# halogen-led.net
KiCad netlist of a schematic drawn in EAGLE
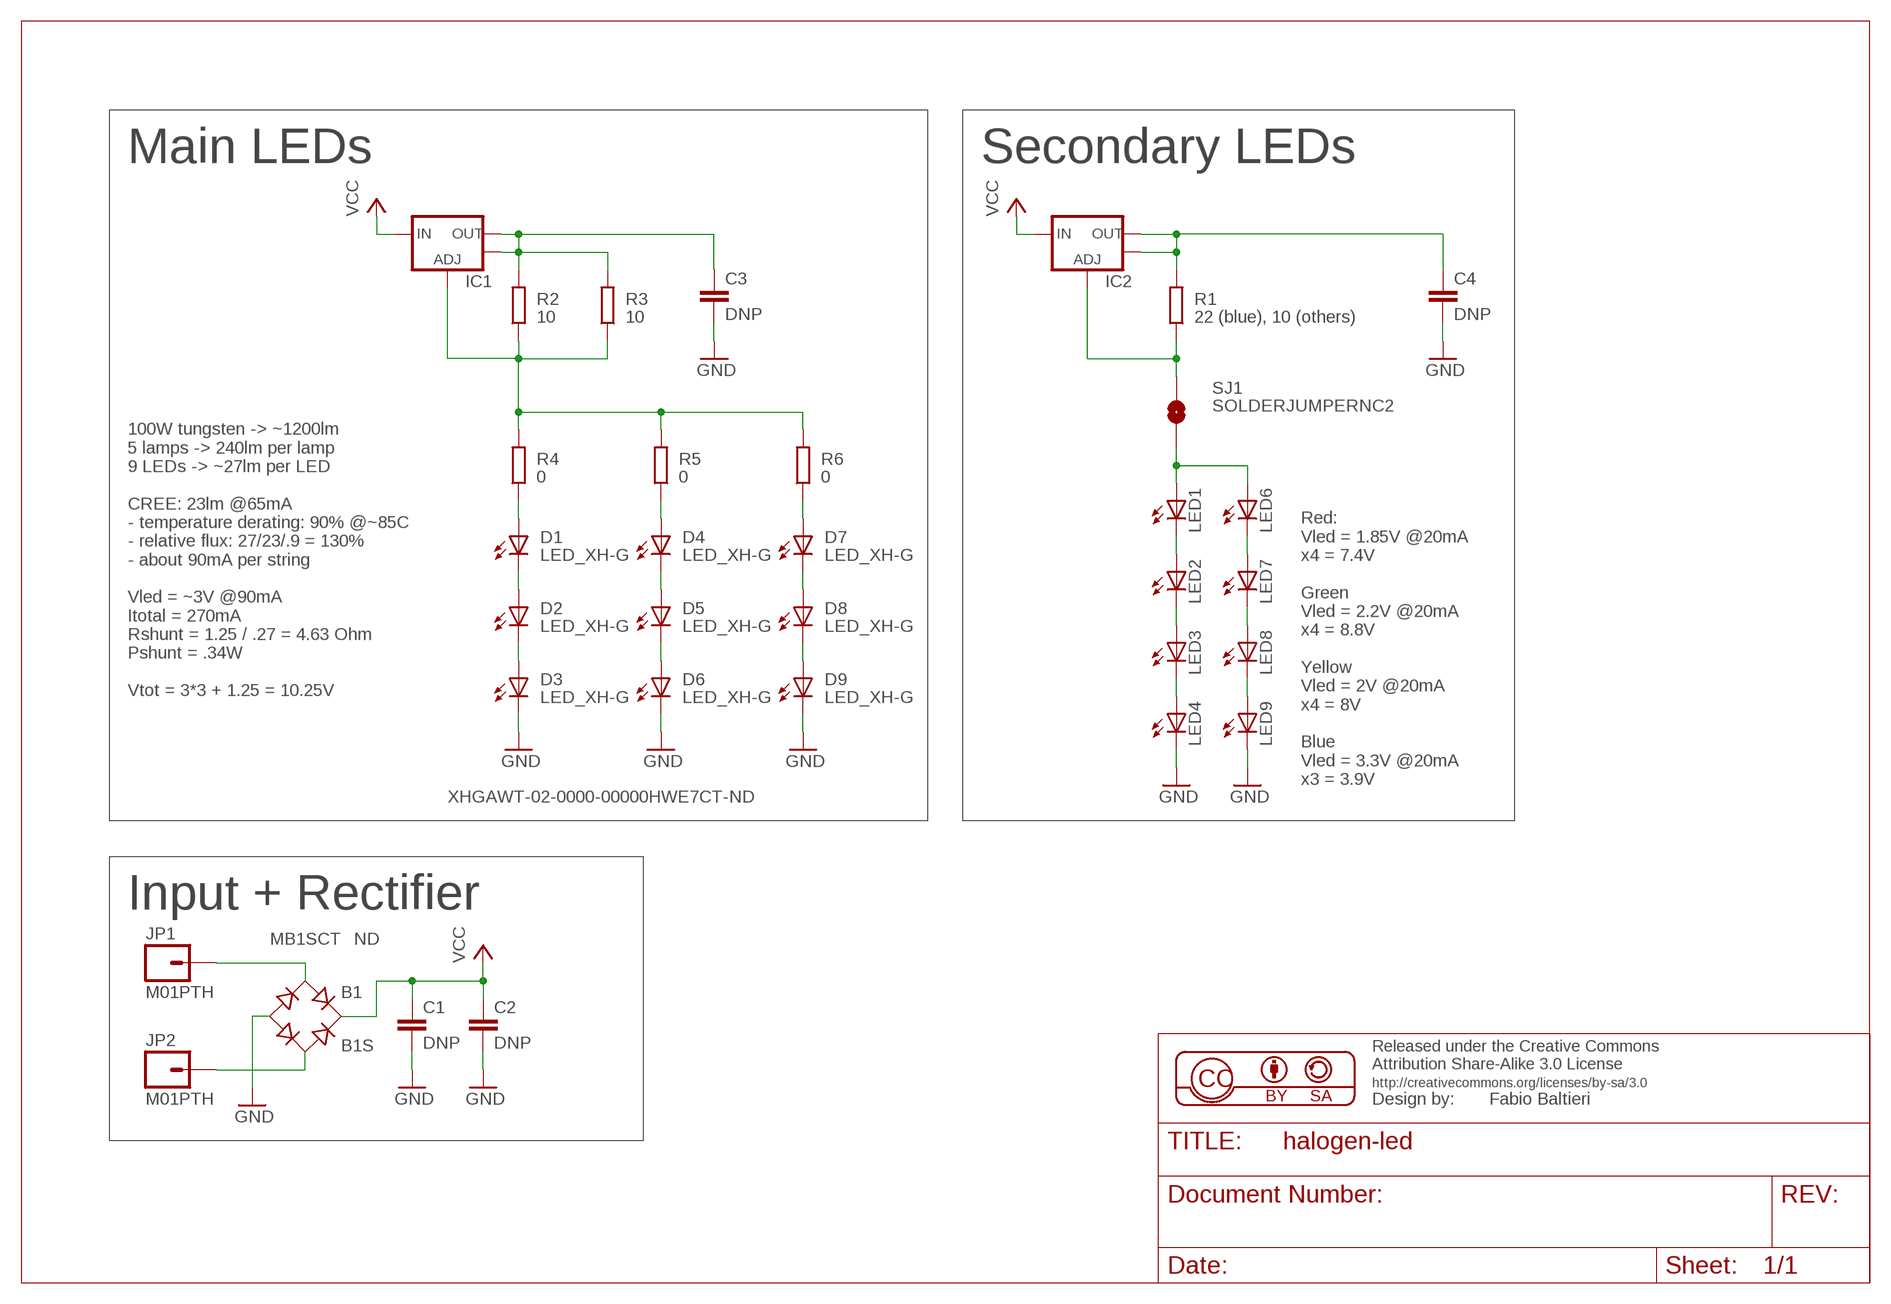
[diagram p0: schematic, sheet 1]

(export (version "E")
  (design (tool "Eeschema 10.0.6"))
  (components
    (comp (ref "B1")
      (value "B1S")
      (footprint "eagle-import:MBS")
      (libsource (lib "eagle-import") (part "BS1"))
    )
    (comp (ref "C1")
      (value "DNP")
      (footprint "eagle-import:C1206")
      (libsource (lib "eagle-import") (part "C-EUC1206"))
    )
    (comp (ref "C2")
      (value "DNP")
      (footprint "eagle-import:C1206")
      (libsource (lib "eagle-import") (part "C-EUC1206"))
    )
    (comp (ref "C3")
      (value "DNP")
      (footprint "eagle-import:C0805")
      (libsource (lib "eagle-import") (part "C-EUC0805"))
    )
    (comp (ref "C4")
      (value "DNP")
      (footprint "eagle-import:C0805")
      (libsource (lib "eagle-import") (part "C-EUC0805"))
    )
    (comp (ref "D1")
      (value "LED_XH-G")
      (footprint "eagle-import:CREE_XHG")
      (libsource (lib "eagle-import") (part "LED_XH-G"))
    )
    (comp (ref "D2")
      (value "LED_XH-G")
      (footprint "eagle-import:CREE_XHG")
      (libsource (lib "eagle-import") (part "LED_XH-G"))
    )
    (comp (ref "D3")
      (value "LED_XH-G")
      (footprint "eagle-import:CREE_XHG")
      (libsource (lib "eagle-import") (part "LED_XH-G"))
    )
    (comp (ref "D4")
      (value "LED_XH-G")
      (footprint "eagle-import:CREE_XHG")
      (libsource (lib "eagle-import") (part "LED_XH-G"))
    )
    (comp (ref "D5")
      (value "LED_XH-G")
      (footprint "eagle-import:CREE_XHG")
      (libsource (lib "eagle-import") (part "LED_XH-G"))
    )
    (comp (ref "D6")
      (value "LED_XH-G")
      (footprint "eagle-import:CREE_XHG")
      (libsource (lib "eagle-import") (part "LED_XH-G"))
    )
    (comp (ref "D7")
      (value "LED_XH-G")
      (footprint "eagle-import:CREE_XHG")
      (libsource (lib "eagle-import") (part "LED_XH-G"))
    )
    (comp (ref "D8")
      (value "LED_XH-G")
      (footprint "eagle-import:CREE_XHG")
      (libsource (lib "eagle-import") (part "LED_XH-G"))
    )
    (comp (ref "D9")
      (value "LED_XH-G")
      (footprint "eagle-import:CREE_XHG")
      (libsource (lib "eagle-import") (part "LED_XH-G"))
    )
    (comp (ref "IC1")
      (value "V_REG_LM1117SOT223")
      (footprint "eagle-import:SOT223")
      (libsource (lib "eagle-import") (part "V_REG_LM1117SOT223"))
    )
    (comp (ref "IC2")
      (value "V_REG_LM1117SOT223")
      (footprint "eagle-import:SOT223")
      (libsource (lib "eagle-import") (part "V_REG_LM1117SOT223"))
    )
    (comp (ref "JP1")
      (value "M01PTH")
      (footprint "eagle-import:1X01")
      (libsource (lib "eagle-import") (part "M01PTH"))
    )
    (comp (ref "JP2")
      (value "M01PTH")
      (footprint "eagle-import:1X01")
      (libsource (lib "eagle-import") (part "M01PTH"))
    )
    (comp (ref "LED1")
      (value "LEDCHIPLED_0805")
      (footprint "eagle-import:CHIPLED_0805")
      (libsource (lib "eagle-import") (part "LEDCHIPLED_0805"))
    )
    (comp (ref "LED2")
      (value "LEDCHIPLED_0805")
      (footprint "eagle-import:CHIPLED_0805")
      (libsource (lib "eagle-import") (part "LEDCHIPLED_0805"))
    )
    (comp (ref "LED3")
      (value "LEDCHIPLED_0805")
      (footprint "eagle-import:CHIPLED_0805")
      (libsource (lib "eagle-import") (part "LEDCHIPLED_0805"))
    )
    (comp (ref "LED4")
      (value "LEDCHIPLED_0805")
      (footprint "eagle-import:CHIPLED_0805")
      (libsource (lib "eagle-import") (part "LEDCHIPLED_0805"))
    )
    (comp (ref "LED6")
      (value "LEDCHIPLED_0805")
      (footprint "eagle-import:CHIPLED_0805")
      (libsource (lib "eagle-import") (part "LEDCHIPLED_0805"))
    )
    (comp (ref "LED7")
      (value "LEDCHIPLED_0805")
      (footprint "eagle-import:CHIPLED_0805")
      (libsource (lib "eagle-import") (part "LEDCHIPLED_0805"))
    )
    (comp (ref "LED8")
      (value "LEDCHIPLED_0805")
      (footprint "eagle-import:CHIPLED_0805")
      (libsource (lib "eagle-import") (part "LEDCHIPLED_0805"))
    )
    (comp (ref "LED9")
      (value "LEDCHIPLED_0805")
      (footprint "eagle-import:CHIPLED_0805")
      (libsource (lib "eagle-import") (part "LEDCHIPLED_0805"))
    )
    (comp (ref "R1")
      (value "22 (blue), 10 (others)")
      (footprint "eagle-import:R1206")
      (libsource (lib "eagle-import") (part "R-EU_R1206"))
    )
    (comp (ref "R2")
      (value "10")
      (footprint "eagle-import:R1206")
      (libsource (lib "eagle-import") (part "R-EU_R1206"))
    )
    (comp (ref "R3")
      (value "10")
      (footprint "eagle-import:R1206")
      (libsource (lib "eagle-import") (part "R-EU_R1206"))
    )
    (comp (ref "R4")
      (value "0")
      (footprint "eagle-import:R0805")
      (libsource (lib "eagle-import") (part "R-EU_R0805"))
    )
    (comp (ref "R5")
      (value "0")
      (footprint "eagle-import:R0805")
      (libsource (lib "eagle-import") (part "R-EU_R0805"))
    )
    (comp (ref "R6")
      (value "0")
      (footprint "eagle-import:R0805")
      (libsource (lib "eagle-import") (part "R-EU_R0805"))
    )
    (comp (ref "SJ1")
      (value "SOLDERJUMPERNC2")
      (footprint "eagle-import:SJ_2S-NOTRACE")
      (libsource (lib "eagle-import") (part "SOLDERJUMPERNC2"))
    )
  )
  (nets
    (net (code "1") (name "GND") (class "Default")
      (node (ref "B1") (pin "-") (pinfunction "-_-") (pintype "passive"))
      (node (ref "C1") (pin "2") (pinfunction "2_2") (pintype "passive"))
      (node (ref "C2") (pin "2") (pinfunction "2_2") (pintype "passive"))
      (node (ref "C3") (pin "2") (pinfunction "2_2") (pintype "passive"))
      (node (ref "C4") (pin "2") (pinfunction "2_2") (pintype "passive"))
      (node (ref "D3") (pin "C") (pinfunction "C_C") (pintype "passive"))
      (node (ref "D3") (pin "C@1") (pinfunction "C_C@1") (pintype "passive"))
      (node (ref "D6") (pin "C") (pinfunction "C_C") (pintype "passive"))
      (node (ref "D6") (pin "C@1") (pinfunction "C_C@1") (pintype "passive"))
      (node (ref "D9") (pin "C") (pinfunction "C_C") (pintype "passive"))
      (node (ref "D9") (pin "C@1") (pinfunction "C_C@1") (pintype "passive"))
      (node (ref "LED4") (pin "C") (pinfunction "C_C") (pintype "passive"))
      (node (ref "LED9") (pin "C") (pinfunction "C_C") (pintype "passive"))
    )
    (net (code "2") (name "Net-(B1-PadAC1)") (class "Default")
      (node (ref "B1") (pin "AC1") (pinfunction "AC1_AC1") (pintype "passive"))
      (node (ref "JP1") (pin "1") (pinfunction "1_1") (pintype "passive"))
    )
    (net (code "3") (name "Net-(B1-PadAC2)") (class "Default")
      (node (ref "B1") (pin "AC2") (pinfunction "AC2_AC2") (pintype "passive"))
      (node (ref "JP2") (pin "1") (pinfunction "1_1") (pintype "passive"))
    )
    (net (code "4") (name "Net-(C3-Pad1)") (class "Default")
      (node (ref "C3") (pin "1") (pinfunction "1_1") (pintype "passive"))
      (node (ref "IC1") (pin "2") (pinfunction "OUT_2") (pintype "output"))
      (node (ref "IC1") (pin "4") (pinfunction "OUT_4") (pintype "output"))
      (node (ref "R2") (pin "2") (pinfunction "2_2") (pintype "passive"))
      (node (ref "R3") (pin "2") (pinfunction "2_2") (pintype "passive"))
    )
    (net (code "5") (name "Net-(C4-Pad1)") (class "Default")
      (node (ref "C4") (pin "1") (pinfunction "1_1") (pintype "passive"))
      (node (ref "IC2") (pin "2") (pinfunction "OUT_2") (pintype "output"))
      (node (ref "IC2") (pin "4") (pinfunction "OUT_4") (pintype "output"))
      (node (ref "R1") (pin "2") (pinfunction "2_2") (pintype "passive"))
    )
    (net (code "6") (name "Net-(D1-A-PadA@1)") (class "Default")
      (node (ref "D1") (pin "A") (pinfunction "A_A") (pintype "passive"))
      (node (ref "D1") (pin "A@1") (pinfunction "A_A@1") (pintype "passive"))
      (node (ref "R4") (pin "1") (pinfunction "1_1") (pintype "passive"))
    )
    (net (code "7") (name "Net-(D1-C-PadC@1)") (class "Default")
      (node (ref "D1") (pin "C") (pinfunction "C_C") (pintype "passive"))
      (node (ref "D1") (pin "C@1") (pinfunction "C_C@1") (pintype "passive"))
      (node (ref "D2") (pin "A") (pinfunction "A_A") (pintype "passive"))
      (node (ref "D2") (pin "A@1") (pinfunction "A_A@1") (pintype "passive"))
    )
    (net (code "8") (name "Net-(D2-C-PadC@1)") (class "Default")
      (node (ref "D2") (pin "C") (pinfunction "C_C") (pintype "passive"))
      (node (ref "D2") (pin "C@1") (pinfunction "C_C@1") (pintype "passive"))
      (node (ref "D3") (pin "A") (pinfunction "A_A") (pintype "passive"))
      (node (ref "D3") (pin "A@1") (pinfunction "A_A@1") (pintype "passive"))
    )
    (net (code "9") (name "Net-(D4-A-PadA@1)") (class "Default")
      (node (ref "D4") (pin "A") (pinfunction "A_A") (pintype "passive"))
      (node (ref "D4") (pin "A@1") (pinfunction "A_A@1") (pintype "passive"))
      (node (ref "R5") (pin "1") (pinfunction "1_1") (pintype "passive"))
    )
    (net (code "10") (name "Net-(D4-C-PadC@1)") (class "Default")
      (node (ref "D4") (pin "C") (pinfunction "C_C") (pintype "passive"))
      (node (ref "D4") (pin "C@1") (pinfunction "C_C@1") (pintype "passive"))
      (node (ref "D5") (pin "A") (pinfunction "A_A") (pintype "passive"))
      (node (ref "D5") (pin "A@1") (pinfunction "A_A@1") (pintype "passive"))
    )
    (net (code "11") (name "Net-(D5-C-PadC@1)") (class "Default")
      (node (ref "D5") (pin "C") (pinfunction "C_C") (pintype "passive"))
      (node (ref "D5") (pin "C@1") (pinfunction "C_C@1") (pintype "passive"))
      (node (ref "D6") (pin "A") (pinfunction "A_A") (pintype "passive"))
      (node (ref "D6") (pin "A@1") (pinfunction "A_A@1") (pintype "passive"))
    )
    (net (code "12") (name "Net-(D7-A-PadA@1)") (class "Default")
      (node (ref "D7") (pin "A") (pinfunction "A_A") (pintype "passive"))
      (node (ref "D7") (pin "A@1") (pinfunction "A_A@1") (pintype "passive"))
      (node (ref "R6") (pin "1") (pinfunction "1_1") (pintype "passive"))
    )
    (net (code "13") (name "Net-(D7-C-PadC@1)") (class "Default")
      (node (ref "D7") (pin "C") (pinfunction "C_C") (pintype "passive"))
      (node (ref "D7") (pin "C@1") (pinfunction "C_C@1") (pintype "passive"))
      (node (ref "D8") (pin "A") (pinfunction "A_A") (pintype "passive"))
      (node (ref "D8") (pin "A@1") (pinfunction "A_A@1") (pintype "passive"))
    )
    (net (code "14") (name "Net-(D8-C-PadC@1)") (class "Default")
      (node (ref "D8") (pin "C") (pinfunction "C_C") (pintype "passive"))
      (node (ref "D8") (pin "C@1") (pinfunction "C_C@1") (pintype "passive"))
      (node (ref "D9") (pin "A") (pinfunction "A_A") (pintype "passive"))
      (node (ref "D9") (pin "A@1") (pinfunction "A_A@1") (pintype "passive"))
    )
    (net (code "15") (name "Net-(IC1-ADJ)") (class "Default")
      (node (ref "IC1") (pin "1") (pinfunction "ADJ_1") (pintype "input"))
      (node (ref "R2") (pin "1") (pinfunction "1_1") (pintype "passive"))
      (node (ref "R3") (pin "1") (pinfunction "1_1") (pintype "passive"))
      (node (ref "R4") (pin "2") (pinfunction "2_2") (pintype "passive"))
      (node (ref "R5") (pin "2") (pinfunction "2_2") (pintype "passive"))
      (node (ref "R6") (pin "2") (pinfunction "2_2") (pintype "passive"))
    )
    (net (code "16") (name "Net-(IC2-ADJ)") (class "Default")
      (node (ref "IC2") (pin "1") (pinfunction "ADJ_1") (pintype "input"))
      (node (ref "R1") (pin "1") (pinfunction "1_1") (pintype "passive"))
      (node (ref "SJ1") (pin "1") (pinfunction "1_1") (pintype "passive"))
    )
    (net (code "17") (name "Net-(LED1-PadA)") (class "Default")
      (node (ref "LED1") (pin "A") (pinfunction "A_A") (pintype "passive"))
      (node (ref "LED6") (pin "A") (pinfunction "A_A") (pintype "passive"))
      (node (ref "SJ1") (pin "2") (pinfunction "2_2") (pintype "passive"))
    )
    (net (code "18") (name "Net-(LED1-PadC)") (class "Default")
      (node (ref "LED1") (pin "C") (pinfunction "C_C") (pintype "passive"))
      (node (ref "LED2") (pin "A") (pinfunction "A_A") (pintype "passive"))
    )
    (net (code "19") (name "Net-(LED2-PadC)") (class "Default")
      (node (ref "LED2") (pin "C") (pinfunction "C_C") (pintype "passive"))
      (node (ref "LED3") (pin "A") (pinfunction "A_A") (pintype "passive"))
    )
    (net (code "20") (name "Net-(LED3-PadC)") (class "Default")
      (node (ref "LED3") (pin "C") (pinfunction "C_C") (pintype "passive"))
      (node (ref "LED4") (pin "A") (pinfunction "A_A") (pintype "passive"))
    )
    (net (code "21") (name "Net-(LED6-PadC)") (class "Default")
      (node (ref "LED6") (pin "C") (pinfunction "C_C") (pintype "passive"))
      (node (ref "LED7") (pin "A") (pinfunction "A_A") (pintype "passive"))
    )
    (net (code "22") (name "Net-(LED7-PadC)") (class "Default")
      (node (ref "LED7") (pin "C") (pinfunction "C_C") (pintype "passive"))
      (node (ref "LED8") (pin "A") (pinfunction "A_A") (pintype "passive"))
    )
    (net (code "23") (name "Net-(LED8-PadC)") (class "Default")
      (node (ref "LED8") (pin "C") (pinfunction "C_C") (pintype "passive"))
      (node (ref "LED9") (pin "A") (pinfunction "A_A") (pintype "passive"))
    )
    (net (code "24") (name "VCC") (class "Default")
      (node (ref "B1") (pin "+") (pinfunction "+_+") (pintype "passive"))
      (node (ref "C1") (pin "1") (pinfunction "1_1") (pintype "passive"))
      (node (ref "C2") (pin "1") (pinfunction "1_1") (pintype "passive"))
      (node (ref "IC1") (pin "3") (pinfunction "IN_3") (pintype "input"))
      (node (ref "IC2") (pin "3") (pinfunction "IN_3") (pintype "input"))
    )
  )
)
